# ZMDI-4-V3.net
KiCad netlist of a schematic drawn in Altium Designer
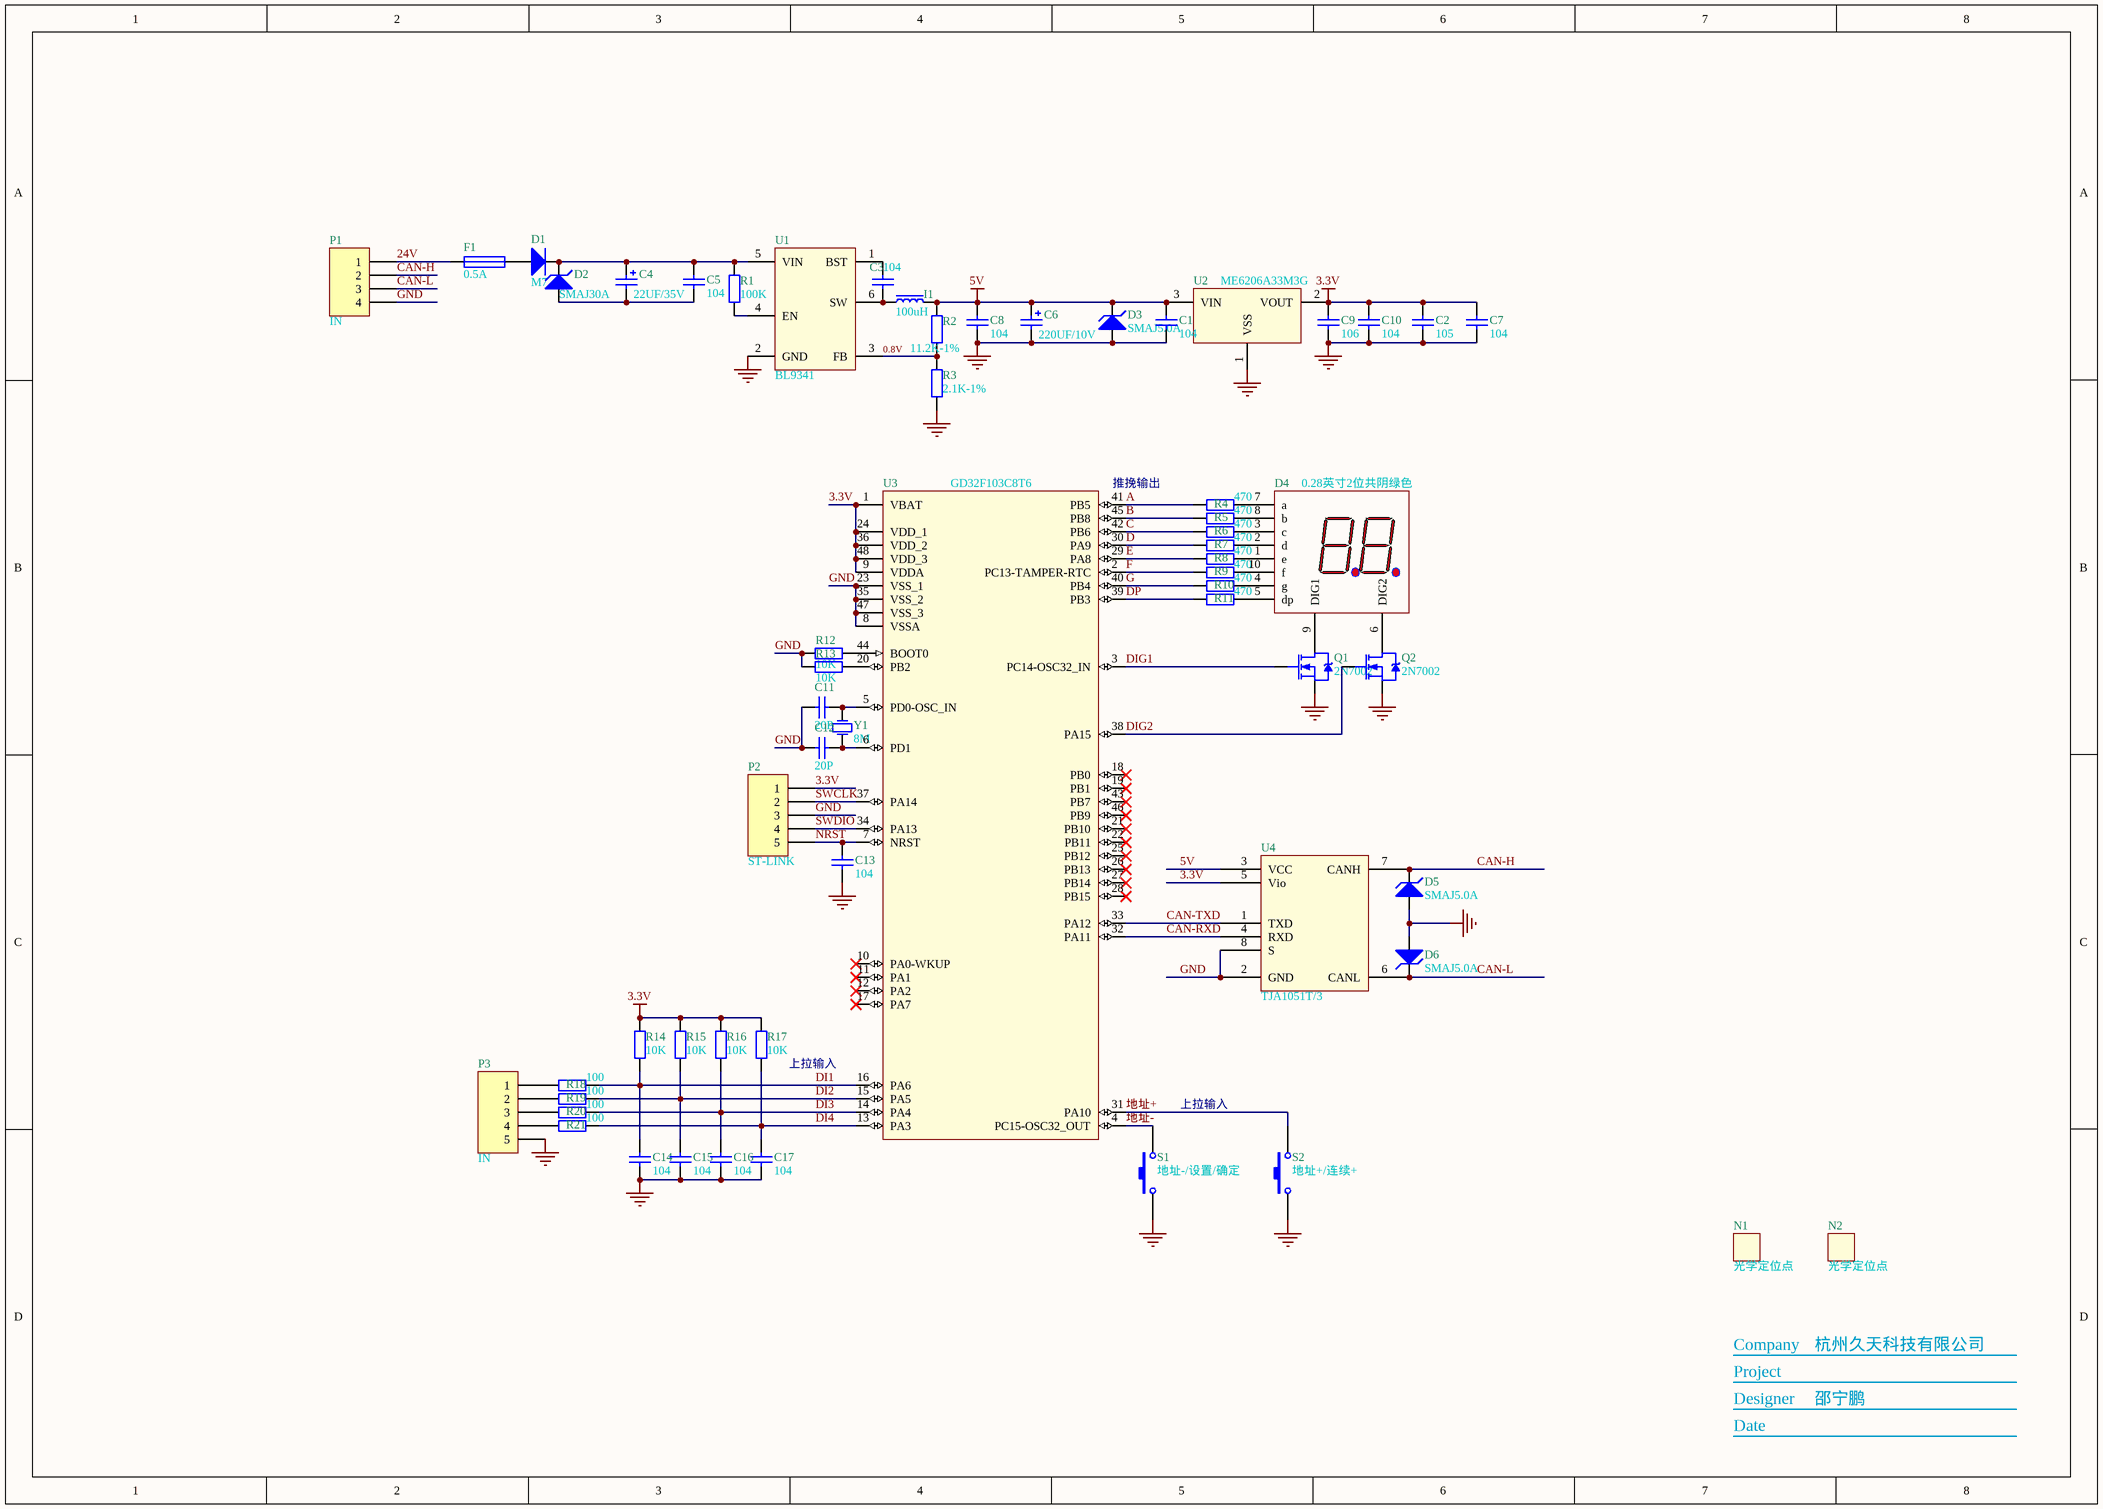
[diagram p0: ZMDI-4-V3.SchDoc]

(export (version "E")
  (design (tool "Eeschema 10.0.6"))
  (components
    (comp (ref "C1")
      (value "104")
      (footprint "C-0603")
      (description "Capacitor")
      (fields (field (name "PUBLISHER") "Altium Limited"))
      (libsource (lib "元件2.0") (part "Cap"))
    )
    (comp (ref "C2")
      (value "105")
      (footprint "C-0603")
      (description "0805")
      (fields (field (name "PUBLISHER") "Altium Limited"))
      (libsource (lib "2电容-V1.0") (part "Cap-0603"))
    )
    (comp (ref "C3")
      (value "104")
      (footprint "C-0603")
      (description "Capacitor")
      (fields (field (name "PUBLISHER") "Altium Limited"))
      (libsource (lib "元件2.0") (part "Cap"))
    )
    (comp (ref "C4")
      (value "22UF/35V")
      (footprint "贴片固态电容5*5.3")
      (description "Polarized Capacitor (Radial)")
      (fields (field (name "PUBLISHER") "Altium Limited"))
      (libsource (lib "元件2.0") (part "Cap Pol1"))
    )
    (comp (ref "C5")
      (value "104")
      (footprint "C-0603")
      (description "Capacitor")
      (fields (field (name "PUBLISHER") "Altium Limited"))
      (libsource (lib "元件2.0") (part "Cap"))
    )
    (comp (ref "C6")
      (value "220UF/10V")
      (footprint "贴片固态电容6.3*5.3-M")
      (description "Polarized Capacitor (Radial)")
      (fields (field (name "PUBLISHER") "Altium Limited"))
      (libsource (lib "元件2.0") (part "Cap Pol1"))
    )
    (comp (ref "C7")
      (value "104")
      (footprint "C-0603")
      (description "0805")
      (fields (field (name "PUBLISHER") "Altium Limited"))
      (libsource (lib "2电容-V1.0") (part "Cap-0603"))
    )
    (comp (ref "C8")
      (value "104")
      (footprint "C-0603")
      (description "Capacitor")
      (fields (field (name "PUBLISHER") "Altium Limited"))
      (libsource (lib "元件2.0") (part "Cap"))
    )
    (comp (ref "C9")
      (value "106")
      (footprint "C-0603")
      (description "0805")
      (fields (field (name "PUBLISHER") "Altium Limited"))
      (libsource (lib "2电容-V1.0") (part "Cap-0603"))
    )
    (comp (ref "C10")
      (value "104")
      (footprint "C-0603")
      (description "0805")
      (fields (field (name "PUBLISHER") "Altium Limited"))
      (libsource (lib "2电容-V1.0") (part "Cap-0603"))
    )
    (comp (ref "C11")
      (value "20P")
      (footprint "C-0603")
      (description "0805")
      (fields (field (name "PUBLISHER") "Altium Limited"))
      (libsource (lib "2电容-V1.0") (part "Cap-0603"))
    )
    (comp (ref "C12")
      (value "20P")
      (footprint "C-0603")
      (description "0805")
      (fields (field (name "PUBLISHER") "Altium Limited"))
      (libsource (lib "2电容-V1.0") (part "Cap-0603"))
    )
    (comp (ref "C13")
      (value "104")
      (footprint "C-0603")
      (description "0805")
      (fields (field (name "PUBLISHER") "Altium Limited"))
      (libsource (lib "2电容-V1.0") (part "Cap-0603"))
    )
    (comp (ref "C14")
      (value "104")
      (footprint "C-0603")
      (description "Capacitor")
      (fields (field (name "PUBLISHER") "Altium Limited"))
      (libsource (lib "元件2.0") (part "Cap"))
    )
    (comp (ref "C15")
      (value "104")
      (footprint "C-0603")
      (description "Capacitor")
      (fields (field (name "PUBLISHER") "Altium Limited"))
      (libsource (lib "元件2.0") (part "Cap"))
    )
    (comp (ref "C16")
      (value "104")
      (footprint "C-0603")
      (description "Capacitor")
      (fields (field (name "PUBLISHER") "Altium Limited"))
      (libsource (lib "元件2.0") (part "Cap"))
    )
    (comp (ref "C17")
      (value "104")
      (footprint "C-0603")
      (description "Capacitor")
      (fields (field (name "PUBLISHER") "Altium Limited"))
      (libsource (lib "元件2.0") (part "Cap"))
    )
    (comp (ref "D1")
      (value "M7")
      (footprint "SMA")
      (description "SMA")
      (fields (field (name "PUBLISHER") "Altium Limited"))
      (libsource (lib "4二极管-V1.1") (part "M7"))
    )
    (comp (ref "D2")
      (value "SMAJ30A")
      (footprint "SMA")
      (description "SMB")
      (libsource (lib "4二极管-V1.1") (part "TVS-1"))
    )
    (comp (ref "D3")
      (value "SMAJ5.0A")
      (footprint "SMA")
      (description "SMB")
      (libsource (lib "4二极管-V1.1") (part "TVS-1"))
    )
    (comp (ref "D4")
      (value "0.28英寸2位共阴绿色")
      (footprint "2位0.28英寸")
      (libsource (lib "7显示屏-V1.0") (part "2位数码管"))
    )
    (comp (ref "D5")
      (value "SMAJ5.0A")
      (footprint "SMA")
      (description "SMB")
      (libsource (lib "4二极管-V1.1") (part "TVS-1"))
    )
    (comp (ref "D6")
      (value "SMAJ5.0A")
      (footprint "SMA")
      (description "SMB")
      (libsource (lib "4二极管-V1.1") (part "TVS-1"))
    )
    (comp (ref "F1")
      (value "0.5A")
      (footprint "FUSE-1808-N")
      (description "Fuse")
      (fields (field (name "PUBLISHER") "Altium Limited"))
      (libsource (lib "11其他元件-V1.0") (part "Fuse 1"))
    )
    (comp (ref "I1")
      (value "100uH")
      (footprint "SWPA4030S")
      (libsource (lib "3电感-V1.0") (part "Inductance3"))
    )
    (comp (ref "N1") (value "光学定位点") (footprint "MARK-1mm-3mm") (libsource (lib "11其他元件-V1.0") (part "无引脚")))
    (comp (ref "N2") (value "光学定位点") (footprint "MARK-1mm-3mm") (libsource (lib "11其他元件-V1.0") (part "无引脚")))
    (comp (ref "P1")
      (value "IN")
      (footprint "KFEDG-3.5-4P-W")
      (description "Header, 4-Pin")
      (fields (field (name "PUBLISHER") "Altium Limited"))
      (libsource (lib "5排针-V1.0") (part "Header 4"))
    )
    (comp (ref "P2")
      (value "ST-LINK")
      (footprint "5P下载口")
      (description "Header, 5-Pin")
      (fields (field (name "PUBLISHER") "Altium Limited"))
      (libsource (lib "5排针-V1.0") (part "Header 5"))
    )
    (comp (ref "P3")
      (value "IN")
      (footprint "XH2.54-5PD")
      (description "Header, 5-Pin")
      (fields (field (name "PUBLISHER") "Altium Limited"))
      (libsource (lib "5排针-V1.0") (part "Header 5"))
    )
    (comp (ref "Q1") (value "2N7002") (footprint "SOT-23") (libsource (lib "4二极管-V1.1") (part "2N7002")))
    (comp (ref "Q2") (value "2N7002") (footprint "SOT-23") (libsource (lib "4二极管-V1.1") (part "2N7002")))
    (comp (ref "R1")
      (value "100K")
      (footprint "R-0603")
      (description "0603")
      (fields (field (name "PUBLISHER") "Altium Limited"))
      (libsource (lib "") (part "Res2-0603_2"))
    )
    (comp (ref "R2")
      (value "11.2K-1%")
      (footprint "R-0603")
      (description "0603")
      (fields (field (name "PUBLISHER") "Altium Limited"))
      (libsource (lib "") (part "Res2-0603_2"))
    )
    (comp (ref "R3")
      (value "2.1K-1%")
      (footprint "R-0603")
      (description "0603")
      (fields (field (name "PUBLISHER") "Altium Limited"))
      (libsource (lib "") (part "Res2-0603_2"))
    )
    (comp (ref "R4")
      (value "470")
      (footprint "R-0603")
      (description "0603")
      (fields (field (name "PUBLISHER") "Altium Limited"))
      (libsource (lib "1电阻-V1.0") (part "Res2-0603"))
    )
    (comp (ref "R5")
      (value "470")
      (footprint "R-0603")
      (description "0603")
      (fields (field (name "PUBLISHER") "Altium Limited"))
      (libsource (lib "1电阻-V1.0") (part "Res2-0603"))
    )
    (comp (ref "R6")
      (value "470")
      (footprint "R-0603")
      (description "0603")
      (fields (field (name "PUBLISHER") "Altium Limited"))
      (libsource (lib "1电阻-V1.0") (part "Res2-0603"))
    )
    (comp (ref "R7")
      (value "470")
      (footprint "R-0603")
      (description "0603")
      (fields (field (name "PUBLISHER") "Altium Limited"))
      (libsource (lib "1电阻-V1.0") (part "Res2-0603"))
    )
    (comp (ref "R8")
      (value "470")
      (footprint "R-0603")
      (description "0603")
      (fields (field (name "PUBLISHER") "Altium Limited"))
      (libsource (lib "1电阻-V1.0") (part "Res2-0603"))
    )
    (comp (ref "R9")
      (value "470")
      (footprint "R-0603")
      (description "0603")
      (fields (field (name "PUBLISHER") "Altium Limited"))
      (libsource (lib "1电阻-V1.0") (part "Res2-0603"))
    )
    (comp (ref "R10")
      (value "470")
      (footprint "R-0603")
      (description "0603")
      (fields (field (name "PUBLISHER") "Altium Limited"))
      (libsource (lib "1电阻-V1.0") (part "Res2-0603"))
    )
    (comp (ref "R11")
      (value "470")
      (footprint "R-0603")
      (description "0603")
      (fields (field (name "PUBLISHER") "Altium Limited"))
      (libsource (lib "1电阻-V1.0") (part "Res2-0603"))
    )
    (comp (ref "R12")
      (value "10K")
      (footprint "R-0603")
      (description "0603")
      (fields (field (name "PUBLISHER") "Altium Limited"))
      (libsource (lib "") (part "Res2-0603_2"))
    )
    (comp (ref "R13")
      (value "10K")
      (footprint "R-0603")
      (description "0603")
      (fields (field (name "PUBLISHER") "Altium Limited"))
      (libsource (lib "") (part "Res2-0603_2"))
    )
    (comp (ref "R14")
      (value "10K")
      (footprint "R-0603")
      (description "0603")
      (fields (field (name "PUBLISHER") "Altium Limited"))
      (libsource (lib "") (part "Res2-0603_1"))
    )
    (comp (ref "R15")
      (value "10K")
      (footprint "R-0603")
      (description "0603")
      (fields (field (name "PUBLISHER") "Altium Limited"))
      (libsource (lib "") (part "Res2-0603_1"))
    )
    (comp (ref "R16")
      (value "10K")
      (footprint "R-0603")
      (description "0603")
      (fields (field (name "PUBLISHER") "Altium Limited"))
      (libsource (lib "") (part "Res2-0603_1"))
    )
    (comp (ref "R17")
      (value "10K")
      (footprint "R-0603")
      (description "0603")
      (fields (field (name "PUBLISHER") "Altium Limited"))
      (libsource (lib "") (part "Res2-0603_1"))
    )
    (comp (ref "R18")
      (value "100")
      (footprint "R-0603")
      (description "0603")
      (fields (field (name "PUBLISHER") "Altium Limited"))
      (libsource (lib "1电阻-V1.0") (part "Res2-0603"))
    )
    (comp (ref "R19")
      (value "100")
      (footprint "R-0603")
      (description "0603")
      (fields (field (name "PUBLISHER") "Altium Limited"))
      (libsource (lib "1电阻-V1.0") (part "Res2-0603"))
    )
    (comp (ref "R20")
      (value "100")
      (footprint "R-0603")
      (description "0603")
      (fields (field (name "PUBLISHER") "Altium Limited"))
      (libsource (lib "1电阻-V1.0") (part "Res2-0603"))
    )
    (comp (ref "R21")
      (value "100")
      (footprint "R-0603")
      (description "0603")
      (fields (field (name "PUBLISHER") "Altium Limited"))
      (libsource (lib "1电阻-V1.0") (part "Res2-0603"))
    )
    (comp (ref "S1")
      (value "地址-/设置/确定")
      (footprint "SB-4.5*4.5*9-L")
      (description "SB-6*6*10")
      (fields (field (name "PUBLISHER") "Altium Limited"))
      (libsource (lib "开关-V1") (part "SB-6*6*9"))
    )
    (comp (ref "S2")
      (value "地址+/连续+")
      (footprint "SB-4.5*4.5*9-L")
      (description "SB-6*6*10")
      (fields (field (name "PUBLISHER") "Altium Limited"))
      (libsource (lib "开关-V1") (part "SB-6*6*9"))
    )
    (comp (ref "U1") (value "BL9341") (footprint "SOT-23-6-N") (libsource (lib "电源芯片DC-DC") (part "BL9341")))
    (comp (ref "U2")
      (value "ME6206A33M3G")
      (footprint "SOT-23")
      (description "LDO稳压 SOT-23")
      (libsource (lib "电源芯片-线性稳压-V1") (part "ME6206A33M3G"))
    )
    (comp (ref "U3")
      (value "GD32F103C8T6")
      (footprint "LQFP48-L")
      (libsource (lib "9单片机-V1.0") (part "GD32F103C8T6"))
    )
    (comp (ref "U4") (value "TJA1051T/3") (footprint "SOP-8-N") (libsource (lib "通讯-V1") (part "TJA1051T/3")))
    (comp (ref "Y1") (value "8M") (footprint "HC-49SMD") (libsource (lib "11其他元件-V1.0") (part "晶振")))
  )
  (nets
    (net (code "1") (name "/0.8V") (class "Default")
      (node (ref "R2") (pin "2") (pinfunction "2_2") (pintype "passive"))
      (node (ref "R3") (pin "1") (pinfunction "1_1") (pintype "passive"))
      (node (ref "U1") (pin "3") (pinfunction "FB_3") (pintype "passive"))
    )
    (net (code "2") (name "/24V") (class "Default")
      (node (ref "F1") (pin "1") (pinfunction "1_1") (pintype "passive"))
      (node (ref "P1") (pin "1") (pinfunction "1_1") (pintype "passive"))
    )
    (net (code "3") (name "/A") (class "Default")
      (node (ref "R4") (pin "1") (pinfunction "1_1") (pintype "passive"))
      (node (ref "U3") (pin "41") (pinfunction "PB5_41") (pintype "bidirectional"))
    )
    (net (code "4") (name "/B") (class "Default")
      (node (ref "R5") (pin "1") (pinfunction "1_1") (pintype "passive"))
      (node (ref "U3") (pin "45") (pinfunction "PB8_45") (pintype "bidirectional"))
    )
    (net (code "5") (name "/C") (class "Default")
      (node (ref "R6") (pin "1") (pinfunction "1_1") (pintype "passive"))
      (node (ref "U3") (pin "42") (pinfunction "PB6_42") (pintype "bidirectional"))
    )
    (net (code "6") (name "/CAN-H") (class "Default")
      (node (ref "D5") (pin "2") (pinfunction "K_2") (pintype "passive"))
      (node (ref "P1") (pin "2") (pinfunction "2_2") (pintype "passive"))
      (node (ref "U4") (pin "7") (pinfunction "CANH_7") (pintype "passive"))
    )
    (net (code "7") (name "/CAN-L") (class "Default")
      (node (ref "D6") (pin "2") (pinfunction "K_2") (pintype "passive"))
      (node (ref "P1") (pin "3") (pinfunction "3_3") (pintype "passive"))
      (node (ref "U4") (pin "6") (pinfunction "CANL_6") (pintype "passive"))
    )
    (net (code "8") (name "/CAN-RXD") (class "Default")
      (node (ref "U3") (pin "32") (pinfunction "PA11_32") (pintype "bidirectional"))
      (node (ref "U4") (pin "4") (pinfunction "RXD_4") (pintype "passive"))
    )
    (net (code "9") (name "/CAN-TXD") (class "Default")
      (node (ref "U3") (pin "33") (pinfunction "PA12_33") (pintype "bidirectional"))
      (node (ref "U4") (pin "1") (pinfunction "TXD_1") (pintype "passive"))
    )
    (net (code "10") (name "/D") (class "Default")
      (node (ref "R7") (pin "1") (pinfunction "1_1") (pintype "passive"))
      (node (ref "U3") (pin "30") (pinfunction "PA9_30") (pintype "bidirectional"))
    )
    (net (code "11") (name "/DI1") (class "Default")
      (node (ref "C14") (pin "2") (pinfunction "2_2") (pintype "passive"))
      (node (ref "R14") (pin "2") (pinfunction "2_2") (pintype "passive"))
      (node (ref "R18") (pin "2") (pinfunction "2_2") (pintype "passive"))
      (node (ref "U3") (pin "16") (pinfunction "PA6_16") (pintype "bidirectional"))
    )
    (net (code "12") (name "/DI2") (class "Default")
      (node (ref "C15") (pin "2") (pinfunction "2_2") (pintype "passive"))
      (node (ref "R15") (pin "2") (pinfunction "2_2") (pintype "passive"))
      (node (ref "R19") (pin "2") (pinfunction "2_2") (pintype "passive"))
      (node (ref "U3") (pin "15") (pinfunction "PA5_15") (pintype "bidirectional"))
    )
    (net (code "13") (name "/DI3") (class "Default")
      (node (ref "C16") (pin "2") (pinfunction "2_2") (pintype "passive"))
      (node (ref "R16") (pin "2") (pinfunction "2_2") (pintype "passive"))
      (node (ref "R20") (pin "2") (pinfunction "2_2") (pintype "passive"))
      (node (ref "U3") (pin "14") (pinfunction "PA4_14") (pintype "bidirectional"))
    )
    (net (code "14") (name "/DI4") (class "Default")
      (node (ref "C17") (pin "2") (pinfunction "2_2") (pintype "passive"))
      (node (ref "R17") (pin "2") (pinfunction "2_2") (pintype "passive"))
      (node (ref "R21") (pin "2") (pinfunction "2_2") (pintype "passive"))
      (node (ref "U3") (pin "13") (pinfunction "PA3_13") (pintype "bidirectional"))
    )
    (net (code "15") (name "/DIG1") (class "Default")
      (node (ref "Q1") (pin "1") (pinfunction "G_1") (pintype "passive"))
      (node (ref "U3") (pin "3") (pinfunction "PC14-OSC32_IN_3") (pintype "bidirectional"))
    )
    (net (code "16") (name "/DIG2") (class "Default")
      (node (ref "Q2") (pin "1") (pinfunction "G_1") (pintype "passive"))
      (node (ref "U3") (pin "38") (pinfunction "PA15_38") (pintype "bidirectional"))
    )
    (net (code "17") (name "/DP") (class "Default")
      (node (ref "R11") (pin "1") (pinfunction "1_1") (pintype "passive"))
      (node (ref "U3") (pin "39") (pinfunction "PB3_39") (pintype "bidirectional"))
    )
    (net (code "18") (name "/E") (class "Default")
      (node (ref "R8") (pin "1") (pinfunction "1_1") (pintype "passive"))
      (node (ref "U3") (pin "29") (pinfunction "PA8_29") (pintype "bidirectional"))
    )
    (net (code "19") (name "/F") (class "Default")
      (node (ref "R9") (pin "1") (pinfunction "1_1") (pintype "passive"))
      (node (ref "U3") (pin "2") (pinfunction "PC13-TAMPER-RTC_2") (pintype "bidirectional"))
    )
    (net (code "20") (name "/G") (class "Default")
      (node (ref "R10") (pin "1") (pinfunction "1_1") (pintype "passive"))
      (node (ref "U3") (pin "40") (pinfunction "PB4_40") (pintype "bidirectional"))
    )
    (net (code "21") (name "/NRST") (class "Default")
      (node (ref "C13") (pin "2") (pinfunction "2_2") (pintype "passive"))
      (node (ref "P2") (pin "5") (pinfunction "5_5") (pintype "passive"))
      (node (ref "U3") (pin "7") (pinfunction "NRST_7") (pintype "bidirectional"))
    )
    (net (code "22") (name "/SWCLK") (class "Default")
      (node (ref "P2") (pin "2") (pinfunction "2_2") (pintype "passive"))
      (node (ref "U3") (pin "37") (pinfunction "PA14_37") (pintype "bidirectional"))
    )
    (net (code "23") (name "/SWDIO") (class "Default")
      (node (ref "P2") (pin "4") (pinfunction "4_4") (pintype "passive"))
      (node (ref "U3") (pin "34") (pinfunction "PA13_34") (pintype "bidirectional"))
    )
    (net (code "24") (name "/地址+") (class "Default")
      (node (ref "S2") (pin "2") (pinfunction "2_2") (pintype "passive"))
      (node (ref "U3") (pin "31") (pinfunction "PA10_31") (pintype "bidirectional"))
    )
    (net (code "25") (name "/地址-") (class "Default")
      (node (ref "S1") (pin "2") (pinfunction "2_2") (pintype "passive"))
      (node (ref "U3") (pin "4") (pinfunction "PC15-OSC32_OUT_4") (pintype "bidirectional"))
    )
    (net (code "26") (name "3.3V") (class "Default")
      (node (ref "C10") (pin "2") (pinfunction "2_2") (pintype "passive"))
      (node (ref "C2") (pin "2") (pinfunction "2_2") (pintype "passive"))
      (node (ref "C7") (pin "2") (pinfunction "2_2") (pintype "passive"))
      (node (ref "C9") (pin "2") (pinfunction "2_2") (pintype "passive"))
      (node (ref "P2") (pin "1") (pinfunction "1_1") (pintype "passive"))
      (node (ref "R14") (pin "1") (pinfunction "1_1") (pintype "passive"))
      (node (ref "R15") (pin "1") (pinfunction "1_1") (pintype "passive"))
      (node (ref "R16") (pin "1") (pinfunction "1_1") (pintype "passive"))
      (node (ref "R17") (pin "1") (pinfunction "1_1") (pintype "passive"))
      (node (ref "U2") (pin "2") (pinfunction "VOUT_2") (pintype "passive"))
      (node (ref "U3") (pin "1") (pinfunction "VBAT_1") (pintype "power_in"))
      (node (ref "U3") (pin "24") (pinfunction "VDD_1_24") (pintype "power_in"))
      (node (ref "U3") (pin "36") (pinfunction "VDD_2_36") (pintype "power_in"))
      (node (ref "U3") (pin "48") (pinfunction "VDD_3_48") (pintype "power_in"))
      (node (ref "U3") (pin "9") (pinfunction "VDDA_9") (pintype "power_in"))
      (node (ref "U4") (pin "5") (pinfunction "Vio_5") (pintype "passive"))
    )
    (net (code "27") (name "5V") (class "Default")
      (node (ref "C1") (pin "2") (pinfunction "2_2") (pintype "passive"))
      (node (ref "C6") (pin "1") (pinfunction "1_1") (pintype "passive"))
      (node (ref "C8") (pin "2") (pinfunction "2_2") (pintype "passive"))
      (node (ref "D3") (pin "2") (pinfunction "K_2") (pintype "passive"))
      (node (ref "I1") (pin "2") (pinfunction "2_2") (pintype "passive"))
      (node (ref "R2") (pin "1") (pinfunction "1_1") (pintype "passive"))
      (node (ref "U2") (pin "3") (pinfunction "VIN_3") (pintype "passive"))
      (node (ref "U4") (pin "3") (pinfunction "VCC_3") (pintype "passive"))
    )
    (net (code "28") (name "GND") (class "Default")
      (node (ref "C1") (pin "1") (pinfunction "1_1") (pintype "passive"))
      (node (ref "C10") (pin "1") (pinfunction "1_1") (pintype "passive"))
      (node (ref "C11") (pin "1") (pinfunction "1_1") (pintype "passive"))
      (node (ref "C12") (pin "1") (pinfunction "1_1") (pintype "passive"))
      (node (ref "C13") (pin "1") (pinfunction "1_1") (pintype "passive"))
      (node (ref "C14") (pin "1") (pinfunction "1_1") (pintype "passive"))
      (node (ref "C15") (pin "1") (pinfunction "1_1") (pintype "passive"))
      (node (ref "C16") (pin "1") (pinfunction "1_1") (pintype "passive"))
      (node (ref "C17") (pin "1") (pinfunction "1_1") (pintype "passive"))
      (node (ref "C2") (pin "1") (pinfunction "1_1") (pintype "passive"))
      (node (ref "C6") (pin "2") (pinfunction "2_2") (pintype "passive"))
      (node (ref "C7") (pin "1") (pinfunction "1_1") (pintype "passive"))
      (node (ref "C8") (pin "1") (pinfunction "1_1") (pintype "passive"))
      (node (ref "C9") (pin "1") (pinfunction "1_1") (pintype "passive"))
      (node (ref "D3") (pin "1") (pinfunction "A_1") (pintype "passive"))
      (node (ref "D5") (pin "1") (pinfunction "A_1") (pintype "passive"))
      (node (ref "D6") (pin "1") (pinfunction "A_1") (pintype "passive"))
      (node (ref "P1") (pin "4") (pinfunction "4_4") (pintype "passive"))
      (node (ref "P2") (pin "3") (pinfunction "3_3") (pintype "passive"))
      (node (ref "P3") (pin "5") (pinfunction "5_5") (pintype "passive"))
      (node (ref "Q1") (pin "2") (pinfunction "S_2") (pintype "passive"))
      (node (ref "Q2") (pin "2") (pinfunction "S_2") (pintype "passive"))
      (node (ref "R12") (pin "2") (pinfunction "2_2") (pintype "passive"))
      (node (ref "R13") (pin "2") (pinfunction "2_2") (pintype "passive"))
      (node (ref "R3") (pin "2") (pinfunction "2_2") (pintype "passive"))
      (node (ref "S1") (pin "1") (pinfunction "1_1") (pintype "passive"))
      (node (ref "S2") (pin "1") (pinfunction "1_1") (pintype "passive"))
      (node (ref "U1") (pin "2") (pinfunction "GND_2") (pintype "passive"))
      (node (ref "U2") (pin "1") (pinfunction "VSS_1") (pintype "passive"))
      (node (ref "U3") (pin "23") (pinfunction "VSS_1_23") (pintype "power_in"))
      (node (ref "U3") (pin "35") (pinfunction "VSS_2_35") (pintype "power_in"))
      (node (ref "U3") (pin "47") (pinfunction "VSS_3_47") (pintype "power_in"))
      (node (ref "U3") (pin "8") (pinfunction "VSSA_8") (pintype "power_in"))
      (node (ref "U4") (pin "2") (pinfunction "GND_2") (pintype "passive"))
      (node (ref "U4") (pin "8") (pinfunction "S_8") (pintype "passive"))
    )
    (net (code "29") (name "Net-(D1-A)") (class "Default")
      (node (ref "D1") (pin "1") (pinfunction "A_1") (pintype "passive"))
      (node (ref "F1") (pin "2") (pinfunction "2_2") (pintype "passive"))
    )
    (net (code "30") (name "Net-(D1-K)") (class "Default")
      (node (ref "C4") (pin "1") (pinfunction "1_1") (pintype "passive"))
      (node (ref "C5") (pin "2") (pinfunction "2_2") (pintype "passive"))
      (node (ref "D1") (pin "2") (pinfunction "K_2") (pintype "passive"))
      (node (ref "D2") (pin "2") (pinfunction "K_2") (pintype "passive"))
      (node (ref "R1") (pin "1") (pinfunction "1_1") (pintype "passive"))
      (node (ref "U1") (pin "5") (pinfunction "VIN_5") (pintype "passive"))
    )
    (net (code "31") (name "Net-(D2-A)") (class "Default")
      (node (ref "C4") (pin "2") (pinfunction "2_2") (pintype "passive"))
      (node (ref "C5") (pin "1") (pinfunction "1_1") (pintype "passive"))
      (node (ref "D2") (pin "1") (pinfunction "A_1") (pintype "passive"))
    )
    (net (code "32") (name "Net-(D4-DIG1)") (class "Default")
      (node (ref "D4") (pin "9") (pinfunction "DIG1_9") (pintype "passive"))
      (node (ref "Q1") (pin "3") (pinfunction "D_3") (pintype "passive"))
    )
    (net (code "33") (name "Net-(D4-DIG2)") (class "Default")
      (node (ref "D4") (pin "6") (pinfunction "DIG2_6") (pintype "passive"))
      (node (ref "Q2") (pin "3") (pinfunction "D_3") (pintype "passive"))
    )
    (net (code "34") (name "Net-(D4-a)") (class "Default")
      (node (ref "D4") (pin "7") (pinfunction "a_7") (pintype "passive"))
      (node (ref "R4") (pin "2") (pinfunction "2_2") (pintype "passive"))
    )
    (net (code "35") (name "Net-(D4-b)") (class "Default")
      (node (ref "D4") (pin "8") (pinfunction "b_8") (pintype "passive"))
      (node (ref "R5") (pin "2") (pinfunction "2_2") (pintype "passive"))
    )
    (net (code "36") (name "Net-(D4-c)") (class "Default")
      (node (ref "D4") (pin "3") (pinfunction "c_3") (pintype "passive"))
      (node (ref "R6") (pin "2") (pinfunction "2_2") (pintype "passive"))
    )
    (net (code "37") (name "Net-(D4-d)") (class "Default")
      (node (ref "D4") (pin "2") (pinfunction "d_2") (pintype "passive"))
      (node (ref "R7") (pin "2") (pinfunction "2_2") (pintype "passive"))
    )
    (net (code "38") (name "Net-(D4-dp)") (class "Default")
      (node (ref "D4") (pin "5") (pinfunction "dp_5") (pintype "passive"))
      (node (ref "R11") (pin "2") (pinfunction "2_2") (pintype "passive"))
    )
    (net (code "39") (name "Net-(D4-e)") (class "Default")
      (node (ref "D4") (pin "1") (pinfunction "e_1") (pintype "passive"))
      (node (ref "R8") (pin "2") (pinfunction "2_2") (pintype "passive"))
    )
    (net (code "40") (name "Net-(D4-f)") (class "Default")
      (node (ref "D4") (pin "10") (pinfunction "f_10") (pintype "passive"))
      (node (ref "R9") (pin "2") (pinfunction "2_2") (pintype "passive"))
    )
    (net (code "41") (name "Net-(D4-g)") (class "Default")
      (node (ref "D4") (pin "4") (pinfunction "g_4") (pintype "passive"))
      (node (ref "R10") (pin "2") (pinfunction "2_2") (pintype "passive"))
    )
    (net (code "42") (name "Net-(P3-Pad1)") (class "Default")
      (node (ref "P3") (pin "1") (pinfunction "1_1") (pintype "passive"))
      (node (ref "R18") (pin "1") (pinfunction "1_1") (pintype "passive"))
    )
    (net (code "43") (name "Net-(P3-Pad2)") (class "Default")
      (node (ref "P3") (pin "2") (pinfunction "2_2") (pintype "passive"))
      (node (ref "R19") (pin "1") (pinfunction "1_1") (pintype "passive"))
    )
    (net (code "44") (name "Net-(P3-Pad3)") (class "Default")
      (node (ref "P3") (pin "3") (pinfunction "3_3") (pintype "passive"))
      (node (ref "R20") (pin "1") (pinfunction "1_1") (pintype "passive"))
    )
    (net (code "45") (name "Net-(P3-Pad4)") (class "Default")
      (node (ref "P3") (pin "4") (pinfunction "4_4") (pintype "passive"))
      (node (ref "R21") (pin "1") (pinfunction "1_1") (pintype "passive"))
    )
    (net (code "46") (name "Net-(U1-BST)") (class "Default")
      (node (ref "C3") (pin "2") (pinfunction "2_2") (pintype "passive"))
      (node (ref "U1") (pin "1") (pinfunction "BST_1") (pintype "passive"))
    )
    (net (code "47") (name "Net-(U1-EN)") (class "Default")
      (node (ref "R1") (pin "2") (pinfunction "2_2") (pintype "passive"))
      (node (ref "U1") (pin "4") (pinfunction "EN_4") (pintype "passive"))
    )
    (net (code "48") (name "Net-(U1-SW)") (class "Default")
      (node (ref "C3") (pin "1") (pinfunction "1_1") (pintype "passive"))
      (node (ref "I1") (pin "1") (pinfunction "1_1") (pintype "passive"))
      (node (ref "U1") (pin "6") (pinfunction "SW_6") (pintype "passive"))
    )
    (net (code "49") (name "Net-(U3-BOOT0)") (class "Default")
      (node (ref "R12") (pin "1") (pinfunction "1_1") (pintype "passive"))
      (node (ref "U3") (pin "44") (pinfunction "BOOT0_44") (pintype "input"))
    )
    (net (code "50") (name "Net-(U3-PB2)") (class "Default")
      (node (ref "R13") (pin "1") (pinfunction "1_1") (pintype "passive"))
      (node (ref "U3") (pin "20") (pinfunction "PB2_20") (pintype "bidirectional"))
    )
    (net (code "51") (name "Net-(U3-PD0-OSC_IN)") (class "Default")
      (node (ref "C11") (pin "2") (pinfunction "2_2") (pintype "passive"))
      (node (ref "U3") (pin "5") (pinfunction "PD0-OSC_IN_5") (pintype "bidirectional"))
      (node (ref "Y1") (pin "2") (pinfunction "OSC2_2") (pintype "passive"))
    )
    (net (code "52") (name "Net-(U3-PD1)") (class "Default")
      (node (ref "C12") (pin "2") (pinfunction "2_2") (pintype "passive"))
      (node (ref "U3") (pin "6") (pinfunction "PD1_6") (pintype "bidirectional"))
      (node (ref "Y1") (pin "1") (pinfunction "OSC1_1") (pintype "passive"))
    )
    (net (code "53") (name "unconnected-(U3-PA0-WKUP-Pad10)") (class "Default")
      (node (ref "U3") (pin "10") (pinfunction "PA0-WKUP_10") (pintype "bidirectional+no_connect"))
    )
    (net (code "54") (name "unconnected-(U3-PA1-Pad11)") (class "Default")
      (node (ref "U3") (pin "11") (pinfunction "PA1_11") (pintype "bidirectional+no_connect"))
    )
    (net (code "55") (name "unconnected-(U3-PA2-Pad12)") (class "Default")
      (node (ref "U3") (pin "12") (pinfunction "PA2_12") (pintype "bidirectional+no_connect"))
    )
    (net (code "56") (name "unconnected-(U3-PA7-Pad17)") (class "Default")
      (node (ref "U3") (pin "17") (pinfunction "PA7_17") (pintype "bidirectional+no_connect"))
    )
    (net (code "57") (name "unconnected-(U3-PB0-Pad18)") (class "Default")
      (node (ref "U3") (pin "18") (pinfunction "PB0_18") (pintype "bidirectional+no_connect"))
    )
    (net (code "58") (name "unconnected-(U3-PB1-Pad19)") (class "Default")
      (node (ref "U3") (pin "19") (pinfunction "PB1_19") (pintype "bidirectional+no_connect"))
    )
    (net (code "59") (name "unconnected-(U3-PB7-Pad43)") (class "Default")
      (node (ref "U3") (pin "43") (pinfunction "PB7_43") (pintype "bidirectional+no_connect"))
    )
    (net (code "60") (name "unconnected-(U3-PB9-Pad46)") (class "Default")
      (node (ref "U3") (pin "46") (pinfunction "PB9_46") (pintype "bidirectional+no_connect"))
    )
    (net (code "61") (name "unconnected-(U3-PB10-Pad21)") (class "Default")
      (node (ref "U3") (pin "21") (pinfunction "PB10_21") (pintype "bidirectional+no_connect"))
    )
    (net (code "62") (name "unconnected-(U3-PB11-Pad22)") (class "Default")
      (node (ref "U3") (pin "22") (pinfunction "PB11_22") (pintype "bidirectional+no_connect"))
    )
    (net (code "63") (name "unconnected-(U3-PB12-Pad25)") (class "Default")
      (node (ref "U3") (pin "25") (pinfunction "PB12_25") (pintype "bidirectional+no_connect"))
    )
    (net (code "64") (name "unconnected-(U3-PB13-Pad26)") (class "Default")
      (node (ref "U3") (pin "26") (pinfunction "PB13_26") (pintype "bidirectional+no_connect"))
    )
    (net (code "65") (name "unconnected-(U3-PB14-Pad27)") (class "Default")
      (node (ref "U3") (pin "27") (pinfunction "PB14_27") (pintype "bidirectional+no_connect"))
    )
    (net (code "66") (name "unconnected-(U3-PB15-Pad28)") (class "Default")
      (node (ref "U3") (pin "28") (pinfunction "PB15_28") (pintype "bidirectional+no_connect"))
    )
  )
)
